# osc.net
KiCad netlist of a schematic drawn in Altium Designer
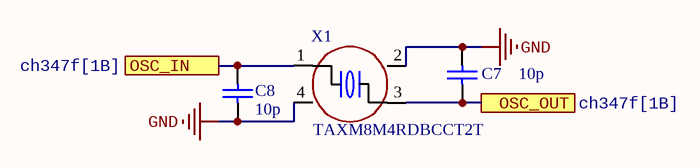
[diagram p0: osc.SchDoc]

(export (version "E")
  (design (tool "Eeschema 10.0.6"))
  (components
    (comp (ref "C7")
      (value "10p")
      (footprint "CAPC100X50X55L25N")
      (fields
        (field (name "MPN") "CC0402JRNPO9BN100")
        (field (name "MANUFACTURER") "YAGEO(国巨)")
        (field (name "Comment") "Capacitor")
      )
      (libsource (lib "std_lib") (part "Capacitor"))
    )
    (comp (ref "C8")
      (value "10p")
      (footprint "CAPC100X50X55L25N")
      (fields
        (field (name "MPN") "CC0402JRNPO9BN100")
        (field (name "MANUFACTURER") "YAGEO(国巨)")
        (field (name "Comment") "Capacitor")
      )
      (libsource (lib "std_lib") (part "Capacitor"))
    )
    (comp (ref "X1")
      (value "TAXM8M4RDBCCT2T")
      (footprint "footprints:OSCCC320X250X80L90X100N")
      (description "8MHz ±10ppm 10pF")
      (fields (field (name "MANUFACTURER") "TAE(雅晶鑫)"))
      (libsource (lib "mcontroller") (part "X32258MSB4SI"))
    )
  )
  (nets
    (net (code "1") (name "/OSC_IN") (class "Default")
      (node (ref "C8") (pin "2") (pinfunction "2_2") (pintype "passive"))
      (node (ref "X1") (pin "1") (pinfunction "1_1") (pintype "passive"))
    )
    (net (code "2") (name "/OSC_OUT") (class "Default")
      (node (ref "C7") (pin "1") (pinfunction "1_1") (pintype "passive"))
      (node (ref "X1") (pin "3") (pinfunction "3_3") (pintype "passive"))
    )
    (net (code "3") (name "GND") (class "Default")
      (node (ref "C7") (pin "2") (pinfunction "2_2") (pintype "passive"))
      (node (ref "C8") (pin "1") (pinfunction "1_1") (pintype "passive"))
      (node (ref "X1") (pin "2") (pinfunction "GND_2") (pintype "passive"))
      (node (ref "X1") (pin "4") (pinfunction "GND_4") (pintype "passive"))
    )
  )
)
